# Lightrelayproject.net
KiCad netlist of a schematic drawn in Altium Designer
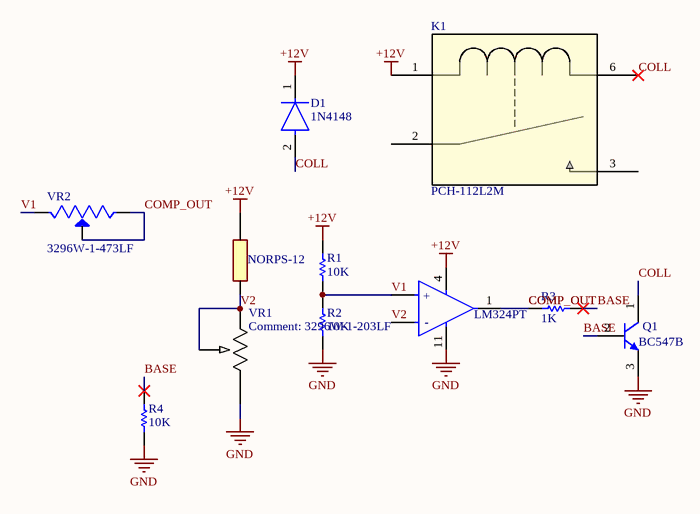
[diagram p0: Lightrelayproject.SchDoc]

(export (version "E")
  (design (tool "Eeschema 10.0.6"))
  (components
    (comp (ref "D1")
      (value "1N4148")
      (footprint "FP-017AG-MFG")
      (description "DIODE GEN PURP 100V 200MA DO35")
      (fields (field (name "VOLTAGE") "100V"))
      (libsource (lib "Altium Content Vault") (part "d7152d700b627762746794eb795d46e"))
    )
    (comp (ref "K1")
      (value "PCH-112L2M")
      (footprint "RELAY_PCH-1A_TYC")
      (description "Description")
      (fields (field (name "COPYRIGHT") "Copyright (C) 2025 Ultra Librarian. All rights reserved."))
      (libsource (lib "PCH-112L2M") (part "PCH-112L2M"))
    )
    (comp (ref "Q1")
      (value "BC547B")
      (footprint "ONSC-TO-92-3-29-11")
      (description "Amplifier Transistor, NPN Silicon, 3-Pin TO-92, Bulk Box")
      (fields (field (name "MANUFACTURER") "On Semiconductor"))
      (libsource (lib "Altium Content Vault") (part "ONSC-NPN-C1B2E3-3"))
    )
    (comp (ref "R1")
      (value "10K")
      (footprint "YAG_CFR25_YAG")
      (description "Resistor")
      (libsource (lib "Simulation Generic Components") (part "Resistor"))
    )
    (comp (ref "R2")
      (value "10K")
      (footprint "YAG_CFR25_YAG")
      (description "Resistor")
      (libsource (lib "Simulation Generic Components") (part "Resistor"))
    )
    (comp (ref "R3")
      (value "1K")
      (footprint "YAG_CFR25_YAG")
      (description "Resistor")
      (libsource (lib "Simulation Generic Components") (part "Resistor"))
    )
    (comp (ref "R4")
      (value "10K")
      (footprint "YAG_CFR25_YAG")
      (description "Resistor")
      (libsource (lib "Simulation Generic Components") (part "Resistor"))
    )
    (comp (ref "U1")
      (value "LM324PT")
      (footprint "FP-TSSOP14-IPC_C")
      (description "IC OPAMP GP 4 CIRCUIT 14TSSOP")
      (libsource (lib "Altium Content Vault") (part "892e52a472e47f7259eef305b851eba"))
    )
    (comp (ref "VR1")
      (value "3296W-1-203LF")
      (footprint "POT_3296W")
      (description "Description")
      (fields (field (name "COPYRIGHT") "Copyright (C) 2025 Ultra Librarian. All rights reserved."))
      (libsource (lib "3296W-1-203LF") (part "3296W-1-203LF"))
    )
    (comp (ref "VR2")
      (value "3296W-1-473LF")
      (footprint "TRIM_3296W-1-473LF")
      (description "47 kOhms 0.5W, 1/2W PC Pins Through Hole Trimmer Potentiometer Cermet 25.0 Turn Top Adjustment")
      (fields (field (name "MF") "Bourns"))
      (libsource (lib "3296W-1-473LF") (part "3296W-1-473LF"))
    )
    (comp (ref "X1")
      (value "NORPS-12")
      (footprint "NORPS12")
      (description "ADVANCED PHOTONIX - NORPS-12 - LIGHT DEPENDENT RESISTOR,1MOHM,250MW")
      (fields (field (name "MOUSER PART NUMBER") "846-NORPS-12"))
      (libsource (lib "NORPS-12") (part "NORPS-12"))
    )
  )
  (nets
    (net (code "1") (name "+12V") (class "Default")
      (node (ref "D1") (pin "1") (pinfunction "C_1") (pintype "passive"))
      (node (ref "K1") (pin "1") (pinfunction "1_1") (pintype "passive"))
      (node (ref "R1") (pin "2") (pinfunction "2_2") (pintype "passive"))
      (node (ref "U1") (pin "4") (pinfunction "VCC+_4") (pintype "power_in"))
      (node (ref "X1") (pin "2") (pinfunction "2_2") (pintype "passive"))
    )
    (net (code "2") (name "/BASE") (class "Default")
      (node (ref "Q1") (pin "2") (pinfunction "B_2") (pintype "passive"))
      (node (ref "R3") (pin "2") (pinfunction "2_2") (pintype "passive"))
      (node (ref "R4") (pin "2") (pinfunction "2_2") (pintype "passive"))
    )
    (net (code "3") (name "/COLL") (class "Default")
      (node (ref "D1") (pin "2") (pinfunction "A_2") (pintype "passive"))
      (node (ref "K1") (pin "6") (pinfunction "4_6") (pintype "passive"))
      (node (ref "Q1") (pin "1") (pinfunction "C_1") (pintype "passive"))
    )
    (net (code "4") (name "/COMP_OUT") (class "Default")
      (node (ref "R3") (pin "1") (pinfunction "1_1") (pintype "passive"))
      (node (ref "U1") (pin "1") (pinfunction "Output_1_1") (pintype "passive"))
      (node (ref "VR2") (pin "1") (pinfunction "CCW_1") (pintype "passive"))
      (node (ref "VR2") (pin "2") (pinfunction "WIPER_2") (pintype "passive"))
    )
    (net (code "5") (name "/V1") (class "Default")
      (node (ref "R1") (pin "1") (pinfunction "1_1") (pintype "passive"))
      (node (ref "R2") (pin "2") (pinfunction "2_2") (pintype "passive"))
      (node (ref "U1") (pin "3") (pinfunction "Non-inverting_input_1_3") (pintype "tri_state"))
      (node (ref "VR2") (pin "3") (pinfunction "CW_3") (pintype "passive"))
    )
    (net (code "6") (name "/V2") (class "Default")
      (node (ref "U1") (pin "2") (pinfunction "Inverting_input_1_2") (pintype "tri_state"))
      (node (ref "VR1") (pin "2") (pinfunction "2_2") (pintype "passive"))
      (node (ref "VR1") (pin "3") (pinfunction "3_3") (pintype "passive"))
      (node (ref "X1") (pin "1") (pinfunction "1_1") (pintype "passive"))
    )
    (net (code "7") (name "GND") (class "Default")
      (node (ref "Q1") (pin "3") (pinfunction "E_3") (pintype "passive"))
      (node (ref "R2") (pin "1") (pinfunction "1_1") (pintype "passive"))
      (node (ref "R4") (pin "1") (pinfunction "1_1") (pintype "passive"))
      (node (ref "U1") (pin "11") (pinfunction "VCC-_11") (pintype "power_in"))
      (node (ref "VR1") (pin "1") (pinfunction "1_1") (pintype "passive"))
    )
    (net (code "8") (name "unconnected-(K1-Pad2)") (class "Default")
      (node (ref "K1") (pin "2") (pinfunction "2_2") (pintype "passive"))
    )
    (net (code "9") (name "unconnected-(K1-Pad3)") (class "Default")
      (node (ref "K1") (pin "3") (pinfunction "3_3") (pintype "passive"))
    )
  )
)
